# arrbot_v0.net
KiCad netlist of a schematic drawn in EAGLE
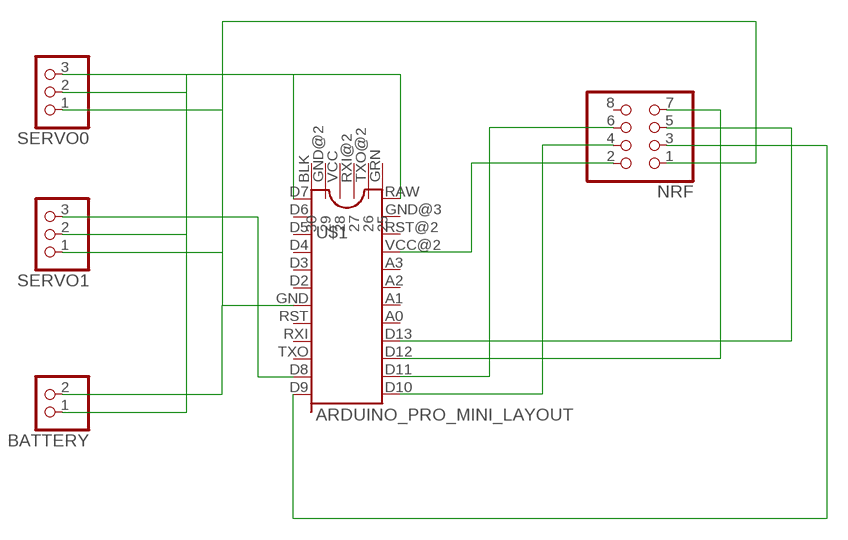
[diagram p0: schematic, sheet 1]

(export (version "E")
  (design (tool "Eeschema 10.0.6"))
  (components
    (comp (ref "BATTERY")
      (value "PINHD-1X2")
      (footprint "eagle-import:1X02")
      (libsource (lib "eagle-import") (part "PINHD-1X2"))
    )
    (comp (ref "NRF")
      (value "PINHD-2X4")
      (footprint "eagle-import:2X04")
      (libsource (lib "eagle-import") (part "PINHD-2X4"))
    )
    (comp (ref "SERVO0")
      (value "PINHD-1X3")
      (footprint "eagle-import:1X03")
      (libsource (lib "eagle-import") (part "PINHD-1X3"))
    )
    (comp (ref "SERVO1")
      (value "PINHD-1X3")
      (footprint "eagle-import:1X03")
      (libsource (lib "eagle-import") (part "PINHD-1X3"))
    )
    (comp (ref "U$1")
      (value "ARDUINO_PRO_MINI_LAYOUT")
      (footprint "eagle-import:ARDUINO_PRO_MINI_PINOUT")
      (libsource (lib "eagle-import") (part "ARDUINO_PRO_MINI_LAYOUT"))
    )
  )
  (nets
    (net (code "1") (name "Net-(U$1-1)") (class "Default")
      (node (ref "SERVO0") (pin "3") (pinfunction "3_3") (pintype "passive"))
      (node (ref "U$1") (pin "D7") (pinfunction "1_D7") (pintype "passive"))
    )
    (net (code "2") (name "Net-(U$1-7)") (class "Default")
      (node (ref "BATTERY") (pin "2") (pinfunction "2_2") (pintype "passive"))
      (node (ref "NRF") (pin "1") (pinfunction "1_1") (pintype "passive"))
      (node (ref "SERVO0") (pin "1") (pinfunction "1_1") (pintype "passive"))
      (node (ref "SERVO1") (pin "1") (pinfunction "1_1") (pintype "passive"))
      (node (ref "U$1") (pin "GND") (pinfunction "7_GND") (pintype "passive"))
    )
    (net (code "3") (name "Net-(U$1-11)") (class "Default")
      (node (ref "SERVO1") (pin "3") (pinfunction "3_3") (pintype "passive"))
      (node (ref "U$1") (pin "D8") (pinfunction "11_D8") (pintype "passive"))
    )
    (net (code "4") (name "Net-(U$1-12)") (class "Default")
      (node (ref "NRF") (pin "3") (pinfunction "3_3") (pintype "passive"))
      (node (ref "U$1") (pin "D9") (pinfunction "12_D9") (pintype "passive"))
    )
    (net (code "5") (name "Net-(U$1-13)") (class "Default")
      (node (ref "NRF") (pin "4") (pinfunction "4_4") (pintype "passive"))
      (node (ref "U$1") (pin "D10") (pinfunction "13_D10") (pintype "passive"))
    )
    (net (code "6") (name "Net-(U$1-14)") (class "Default")
      (node (ref "NRF") (pin "6") (pinfunction "6_6") (pintype "passive"))
      (node (ref "U$1") (pin "D11") (pinfunction "14_D11") (pintype "passive"))
    )
    (net (code "7") (name "Net-(U$1-15)") (class "Default")
      (node (ref "NRF") (pin "7") (pinfunction "7_7") (pintype "passive"))
      (node (ref "U$1") (pin "D12") (pinfunction "15_D12") (pintype "passive"))
    )
    (net (code "8") (name "Net-(U$1-16)") (class "Default")
      (node (ref "NRF") (pin "5") (pinfunction "5_5") (pintype "passive"))
      (node (ref "U$1") (pin "D13") (pinfunction "16_D13") (pintype "passive"))
    )
    (net (code "9") (name "Net-(U$1-21)") (class "Default")
      (node (ref "NRF") (pin "2") (pinfunction "2_2") (pintype "passive"))
      (node (ref "U$1") (pin "VCC@2") (pinfunction "21_VCC@2") (pintype "passive"))
    )
    (net (code "10") (name "Net-(U$1-24)") (class "Default")
      (node (ref "BATTERY") (pin "1") (pinfunction "1_1") (pintype "passive"))
      (node (ref "SERVO0") (pin "2") (pinfunction "2_2") (pintype "passive"))
      (node (ref "SERVO1") (pin "2") (pinfunction "2_2") (pintype "passive"))
      (node (ref "U$1") (pin "RAW") (pinfunction "24_RAW") (pintype "passive"))
    )
    (net (code "11") (name "unconnected-(NRF-Pad8)") (class "Default")
      (node (ref "NRF") (pin "8") (pinfunction "8_8") (pintype "passive"))
    )
    (net (code "12") (name "unconnected-(U$1-2-PadD6)") (class "Default")
      (node (ref "U$1") (pin "D6") (pinfunction "2_D6") (pintype "passive"))
    )
    (net (code "13") (name "unconnected-(U$1-3-PadD5)") (class "Default")
      (node (ref "U$1") (pin "D5") (pinfunction "3_D5") (pintype "passive"))
    )
    (net (code "14") (name "unconnected-(U$1-4-PadD4)") (class "Default")
      (node (ref "U$1") (pin "D4") (pinfunction "4_D4") (pintype "passive"))
    )
    (net (code "15") (name "unconnected-(U$1-5-PadD3)") (class "Default")
      (node (ref "U$1") (pin "D3") (pinfunction "5_D3") (pintype "passive"))
    )
    (net (code "16") (name "unconnected-(U$1-6-PadD2)") (class "Default")
      (node (ref "U$1") (pin "D2") (pinfunction "6_D2") (pintype "passive"))
    )
    (net (code "17") (name "unconnected-(U$1-8-PadRST)") (class "Default")
      (node (ref "U$1") (pin "RST") (pinfunction "8_RST") (pintype "passive"))
    )
    (net (code "18") (name "unconnected-(U$1-9-PadRXI)") (class "Default")
      (node (ref "U$1") (pin "RXI") (pinfunction "9_RXI") (pintype "passive"))
    )
    (net (code "19") (name "unconnected-(U$1-10-PadTXO)") (class "Default")
      (node (ref "U$1") (pin "TXO") (pinfunction "10_TXO") (pintype "passive"))
    )
    (net (code "20") (name "unconnected-(U$1-17-PadA0)") (class "Default")
      (node (ref "U$1") (pin "A0") (pinfunction "17_A0") (pintype "passive"))
    )
    (net (code "21") (name "unconnected-(U$1-18-PadA1)") (class "Default")
      (node (ref "U$1") (pin "A1") (pinfunction "18_A1") (pintype "passive"))
    )
    (net (code "22") (name "unconnected-(U$1-19-PadA2)") (class "Default")
      (node (ref "U$1") (pin "A2") (pinfunction "19_A2") (pintype "passive"))
    )
    (net (code "23") (name "unconnected-(U$1-20-PadA3)") (class "Default")
      (node (ref "U$1") (pin "A3") (pinfunction "20_A3") (pintype "passive"))
    )
    (net (code "24") (name "unconnected-(U$1-22-PadRST@2)") (class "Default")
      (node (ref "U$1") (pin "RST@2") (pinfunction "22_RST@2") (pintype "passive"))
    )
    (net (code "25") (name "unconnected-(U$1-23-PadGND@3)") (class "Default")
      (node (ref "U$1") (pin "GND@3") (pinfunction "23_GND@3") (pintype "passive"))
    )
    (net (code "26") (name "unconnected-(U$1-25-PadGRN)") (class "Default")
      (node (ref "U$1") (pin "GRN") (pinfunction "25_GRN") (pintype "bidirectional"))
    )
    (net (code "27") (name "unconnected-(U$1-26-PadTXO@2)") (class "Default")
      (node (ref "U$1") (pin "TXO@2") (pinfunction "26_TXO@2") (pintype "bidirectional"))
    )
    (net (code "28") (name "unconnected-(U$1-27-PadRXI@2)") (class "Default")
      (node (ref "U$1") (pin "RXI@2") (pinfunction "27_RXI@2") (pintype "bidirectional"))
    )
    (net (code "29") (name "unconnected-(U$1-28-PadVCC)") (class "Default")
      (node (ref "U$1") (pin "VCC") (pinfunction "28_VCC") (pintype "bidirectional"))
    )
    (net (code "30") (name "unconnected-(U$1-29-PadGND@2)") (class "Default")
      (node (ref "U$1") (pin "GND@2") (pinfunction "29_GND@2") (pintype "bidirectional"))
    )
    (net (code "31") (name "unconnected-(U$1-30-PadBLK)") (class "Default")
      (node (ref "U$1") (pin "BLK") (pinfunction "30_BLK") (pintype "bidirectional"))
    )
  )
)
